# POWER.net
KiCad netlist of a schematic drawn in Altium Designer
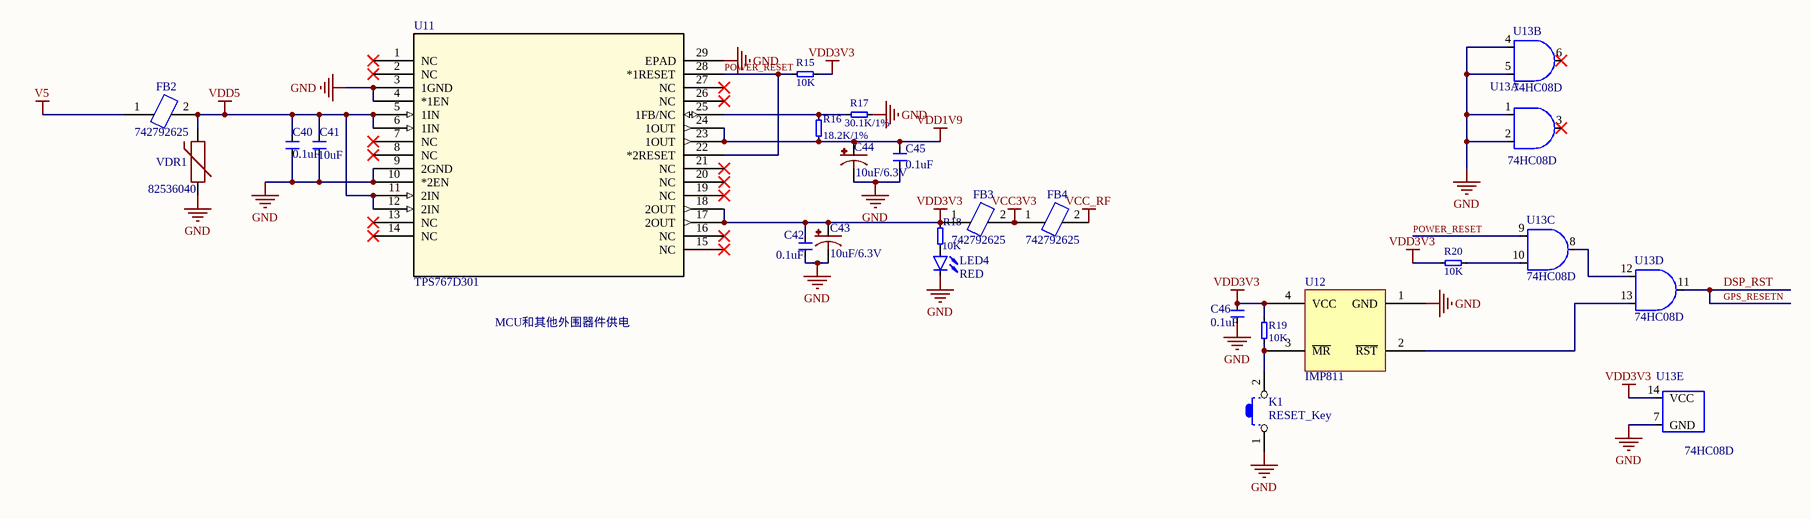
[diagram p0: POWER.SchDoc]

(export (version "E")
  (design (tool "Eeschema 10.0.6"))
  (components
    (comp (ref "C40") (value "0.1uF") (footprint "0603C") (libsource (lib "研发中心原理图库文件") (part "C")))
    (comp (ref "C41") (value "10uF") (footprint "0603C") (libsource (lib "研发中心原理图库文件") (part "C")))
    (comp (ref "C42") (value "0.1uF") (footprint "0603C") (libsource (lib "研发中心原理图库文件") (part "C")))
    (comp (ref "C43")
      (value "10uF/6.3V")
      (footprint "3216/A")
      (libsource (lib "研发中心原理图库文件") (part "C-POLAR"))
    )
    (comp (ref "C44")
      (value "10uF/6.3V")
      (footprint "3216/A")
      (libsource (lib "研发中心原理图库文件") (part "C-POLAR"))
    )
    (comp (ref "C45") (value "0.1uF") (footprint "0603C") (libsource (lib "研发中心原理图库文件") (part "C")))
    (comp (ref "C46") (value "0.1uF") (footprint "0603C") (libsource (lib "研发中心原理图库文件") (part "C")))
    (comp (ref "FB2")
      (value "742792625")
      (footprint "研发中心PCB库文件:0603-FB")
      (libsource (lib "研发中心原理图库文件") (part "FB"))
    )
    (comp (ref "FB3")
      (value "742792625")
      (footprint "研发中心PCB库文件:0603-FB")
      (libsource (lib "研发中心原理图库文件") (part "FB"))
    )
    (comp (ref "FB4")
      (value "742792625")
      (footprint "研发中心PCB库文件:0603-FB")
      (libsource (lib "研发中心原理图库文件") (part "FB"))
    )
    (comp (ref "K1")
      (value "RESET_Key")
      (footprint "研发中心PCB库文件:KEY(2*4*3.5)")
      (libsource (lib "研发中心原理图库文件") (part "RESET_Key"))
    )
    (comp (ref "LED4") (value "RED") (footprint "0603D") (libsource (lib "研发中心原理图库文件") (part "LED")))
    (comp (ref "R15") (value "10K") (footprint "0603R") (libsource (lib "研发中心原理图库文件") (part "R")))
    (comp (ref "R16") (value "18.2K/1%") (footprint "0603R") (libsource (lib "研发中心原理图库文件") (part "R")))
    (comp (ref "R17") (value "30.1K/1%") (footprint "0603R") (libsource (lib "研发中心原理图库文件") (part "R")))
    (comp (ref "R18") (value "10K") (footprint "0603R") (libsource (lib "研发中心原理图库文件") (part "R")))
    (comp (ref "R19") (value "10K") (footprint "0603R") (libsource (lib "研发中心原理图库文件") (part "R")))
    (comp (ref "R20") (value "10K") (footprint "0603R") (libsource (lib "研发中心原理图库文件") (part "R")))
    (comp (ref "U11")
      (value "TPS767D301")
      (footprint "研发中心PCB库文件:TPS767D301")
      (libsource (lib "研发中心原理图库文件") (part "TPS767D301"))
    )
    (comp (ref "U12") (value "IMP811") (footprint "IMP811") (libsource (lib "研发中心原理图库文件") (part "IMP811")))
    (comp (ref "U13")
      (value "74HC08D")
      (footprint "TSSOP14")
      (description "2-INPUT AND GATE")
      (libsource (lib "研发中心原理图库文件") (part "74HC08D"))
    )
    (comp (ref "VDR1")
      (value "82536040")
      (footprint "0603R")
      (libsource (lib "研发中心原理图库文件") (part "Varistor"))
    )
  )
  (nets
    (net (code "1") (name "/DSP_RST") (class "Default") (node (ref "U13") (pin "11") (pintype "passive")))
    (net (code "2") (name "/POWER_RESET") (class "Default")
      (node (ref "R15") (pin "1") (pintype "passive"))
      (node (ref "U11") (pin "22") (pinfunction "*2RESET_22") (pintype "passive"))
      (node (ref "U11") (pin "28") (pinfunction "*1RESET_28") (pintype "passive"))
      (node (ref "U13") (pin "9") (pintype "passive"))
    )
    (net (code "3") (name "GND") (class "Default")
      (node (ref "C40") (pin "1") (pintype "passive"))
      (node (ref "C41") (pin "1") (pintype "passive"))
      (node (ref "C42") (pin "1") (pintype "passive"))
      (node (ref "C43") (pin "2") (pinfunction "2_2") (pintype "passive"))
      (node (ref "C44") (pin "2") (pinfunction "2_2") (pintype "passive"))
      (node (ref "C45") (pin "1") (pintype "passive"))
      (node (ref "C46") (pin "1") (pintype "passive"))
      (node (ref "K1") (pin "1") (pinfunction "1_1") (pintype "passive"))
      (node (ref "LED4") (pin "2") (pinfunction "2_2") (pintype "passive"))
      (node (ref "R17") (pin "1") (pintype "passive"))
      (node (ref "U11") (pin "10") (pinfunction "*2EN_10") (pintype "passive"))
      (node (ref "U11") (pin "29") (pinfunction "EPAD_29") (pintype "passive"))
      (node (ref "U11") (pin "3") (pinfunction "1GND_3") (pintype "power_in"))
      (node (ref "U11") (pin "4") (pinfunction "*1EN_4") (pintype "passive"))
      (node (ref "U11") (pin "9") (pinfunction "2GND_9") (pintype "power_in"))
      (node (ref "U12") (pin "1") (pinfunction "GND_1") (pintype "passive"))
      (node (ref "U13") (pin "1") (pintype "passive"))
      (node (ref "U13") (pin "2") (pintype "passive"))
      (node (ref "U13") (pin "4") (pintype "passive"))
      (node (ref "U13") (pin "5") (pintype "passive"))
      (node (ref "U13") (pin "7") (pinfunction "GND_7") (pintype "passive"))
      (node (ref "VDR1") (pin "1") (pinfunction "1_1") (pintype "passive"))
    )
    (net (code "4") (name "Net-(LED4-Pad1)") (class "Default")
      (node (ref "LED4") (pin "1") (pinfunction "1_1") (pintype "passive"))
      (node (ref "R18") (pin "1") (pintype "passive"))
    )
    (net (code "5") (name "Net-(R20-Pad1)") (class "Default")
      (node (ref "R20") (pin "1") (pintype "passive"))
      (node (ref "U13") (pin "10") (pintype "passive"))
    )
    (net (code "6") (name "Net-(U11-1FB{slash}NC)") (class "Default")
      (node (ref "R16") (pin "2") (pintype "passive"))
      (node (ref "R17") (pin "2") (pintype "passive"))
      (node (ref "U11") (pin "25") (pinfunction "1FB/NC_25") (pintype "bidirectional"))
    )
    (net (code "7") (name "Net-(U12-~{MR})") (class "Default")
      (node (ref "K1") (pin "2") (pinfunction "2_2") (pintype "passive"))
      (node (ref "R19") (pin "1") (pintype "passive"))
      (node (ref "U12") (pin "3") (pinfunction "~{MR}_3") (pintype "passive"))
    )
    (net (code "8") (name "Net-(U12-~{RST})") (class "Default")
      (node (ref "U12") (pin "2") (pinfunction "~{RST}_2") (pintype "passive"))
      (node (ref "U13") (pin "13") (pintype "passive"))
    )
    (net (code "9") (name "Net-(U13-Pad12)") (class "Default")
      (node (ref "U13") (pin "12") (pintype "passive"))
      (node (ref "U13") (pin "8") (pintype "passive"))
    )
    (net (code "10") (name "V5") (class "Default")
      (node (ref "FB2") (pin "1") (pinfunction "1_1") (pintype "passive"))
    )
    (net (code "11") (name "VCC3V3") (class "Default")
      (node (ref "FB3") (pin "2") (pinfunction "2_2") (pintype "passive"))
      (node (ref "FB4") (pin "1") (pinfunction "1_1") (pintype "passive"))
    )
    (net (code "12") (name "VCC_RF") (class "Default")
      (node (ref "FB4") (pin "2") (pinfunction "2_2") (pintype "passive"))
    )
    (net (code "13") (name "VDD1V9") (class "Default")
      (node (ref "C44") (pin "1") (pinfunction "1_1") (pintype "passive"))
      (node (ref "C45") (pin "2") (pintype "passive"))
      (node (ref "R16") (pin "1") (pintype "passive"))
      (node (ref "U11") (pin "23") (pinfunction "1OUT_23") (pintype "output"))
      (node (ref "U11") (pin "24") (pinfunction "1OUT_24") (pintype "output"))
    )
    (net (code "14") (name "VDD3V3") (class "Default")
      (node (ref "C42") (pin "2") (pintype "passive"))
      (node (ref "C43") (pin "1") (pinfunction "1_1") (pintype "passive"))
      (node (ref "C46") (pin "2") (pintype "passive"))
      (node (ref "FB3") (pin "1") (pinfunction "1_1") (pintype "passive"))
      (node (ref "R15") (pin "2") (pintype "passive"))
      (node (ref "R18") (pin "2") (pintype "passive"))
      (node (ref "R19") (pin "2") (pintype "passive"))
      (node (ref "R20") (pin "2") (pintype "passive"))
      (node (ref "U11") (pin "17") (pinfunction "2OUT_17") (pintype "output"))
      (node (ref "U11") (pin "18") (pinfunction "2OUT_18") (pintype "output"))
      (node (ref "U12") (pin "4") (pinfunction "VCC_4") (pintype "passive"))
      (node (ref "U13") (pin "14") (pinfunction "VCC_14") (pintype "passive"))
    )
    (net (code "15") (name "VDD5") (class "Default")
      (node (ref "C40") (pin "2") (pintype "passive"))
      (node (ref "C41") (pin "2") (pintype "passive"))
      (node (ref "FB2") (pin "2") (pinfunction "2_2") (pintype "passive"))
      (node (ref "U11") (pin "11") (pinfunction "2IN_11") (pintype "input"))
      (node (ref "U11") (pin "12") (pinfunction "2IN_12") (pintype "input"))
      (node (ref "U11") (pin "5") (pinfunction "1IN_5") (pintype "input"))
      (node (ref "U11") (pin "6") (pinfunction "1IN_6") (pintype "input"))
      (node (ref "VDR1") (pin "2") (pinfunction "2_2") (pintype "passive"))
    )
    (net (code "16") (name "unconnected-(U11-NC-Pad1)") (class "Default")
      (node (ref "U11") (pin "1") (pinfunction "NC_1") (pintype "passive+no_connect"))
    )
    (net (code "17") (name "unconnected-(U11-NC-Pad2)") (class "Default")
      (node (ref "U11") (pin "2") (pinfunction "NC_2") (pintype "passive+no_connect"))
    )
    (net (code "18") (name "unconnected-(U11-NC-Pad7)") (class "Default")
      (node (ref "U11") (pin "7") (pinfunction "NC_7") (pintype "passive+no_connect"))
    )
    (net (code "19") (name "unconnected-(U11-NC-Pad8)") (class "Default")
      (node (ref "U11") (pin "8") (pinfunction "NC_8") (pintype "passive+no_connect"))
    )
    (net (code "20") (name "unconnected-(U11-NC-Pad13)") (class "Default")
      (node (ref "U11") (pin "13") (pinfunction "NC_13") (pintype "passive+no_connect"))
    )
    (net (code "21") (name "unconnected-(U11-NC-Pad14)") (class "Default")
      (node (ref "U11") (pin "14") (pinfunction "NC_14") (pintype "passive+no_connect"))
    )
    (net (code "22") (name "unconnected-(U11-NC-Pad15)") (class "Default")
      (node (ref "U11") (pin "15") (pinfunction "NC_15") (pintype "passive+no_connect"))
    )
    (net (code "23") (name "unconnected-(U11-NC-Pad16)") (class "Default")
      (node (ref "U11") (pin "16") (pinfunction "NC_16") (pintype "passive+no_connect"))
    )
    (net (code "24") (name "unconnected-(U11-NC-Pad19)") (class "Default")
      (node (ref "U11") (pin "19") (pinfunction "NC_19") (pintype "passive+no_connect"))
    )
    (net (code "25") (name "unconnected-(U11-NC-Pad20)") (class "Default")
      (node (ref "U11") (pin "20") (pinfunction "NC_20") (pintype "passive+no_connect"))
    )
    (net (code "26") (name "unconnected-(U11-NC-Pad21)") (class "Default")
      (node (ref "U11") (pin "21") (pinfunction "NC_21") (pintype "passive+no_connect"))
    )
    (net (code "27") (name "unconnected-(U11-NC-Pad26)") (class "Default")
      (node (ref "U11") (pin "26") (pinfunction "NC_26") (pintype "passive+no_connect"))
    )
    (net (code "28") (name "unconnected-(U11-NC-Pad27)") (class "Default")
      (node (ref "U11") (pin "27") (pinfunction "NC_27") (pintype "passive+no_connect"))
    )
    (net (code "29") (name "unconnected-(U13-Pad3)") (class "Default")
      (node (ref "U13") (pin "3") (pintype "passive+no_connect"))
    )
    (net (code "30") (name "unconnected-(U13-Pad6)") (class "Default")
      (node (ref "U13") (pin "6") (pintype "passive+no_connect"))
    )
    (net (code "31") (name "unconnected-(U13A-GND-Pad7)") (class "Default")
      (node (ref "U13") (pin "7") (pinfunction "GND_7") (pintype "passive"))
    )
    (net (code "32") (name "unconnected-(U13A-VCC-Pad14)") (class "Default")
      (node (ref "U13") (pin "14") (pinfunction "VCC_14") (pintype "passive"))
    )
  )
)
